# f103.net
KiCad netlist of a schematic drawn in Altium Designer
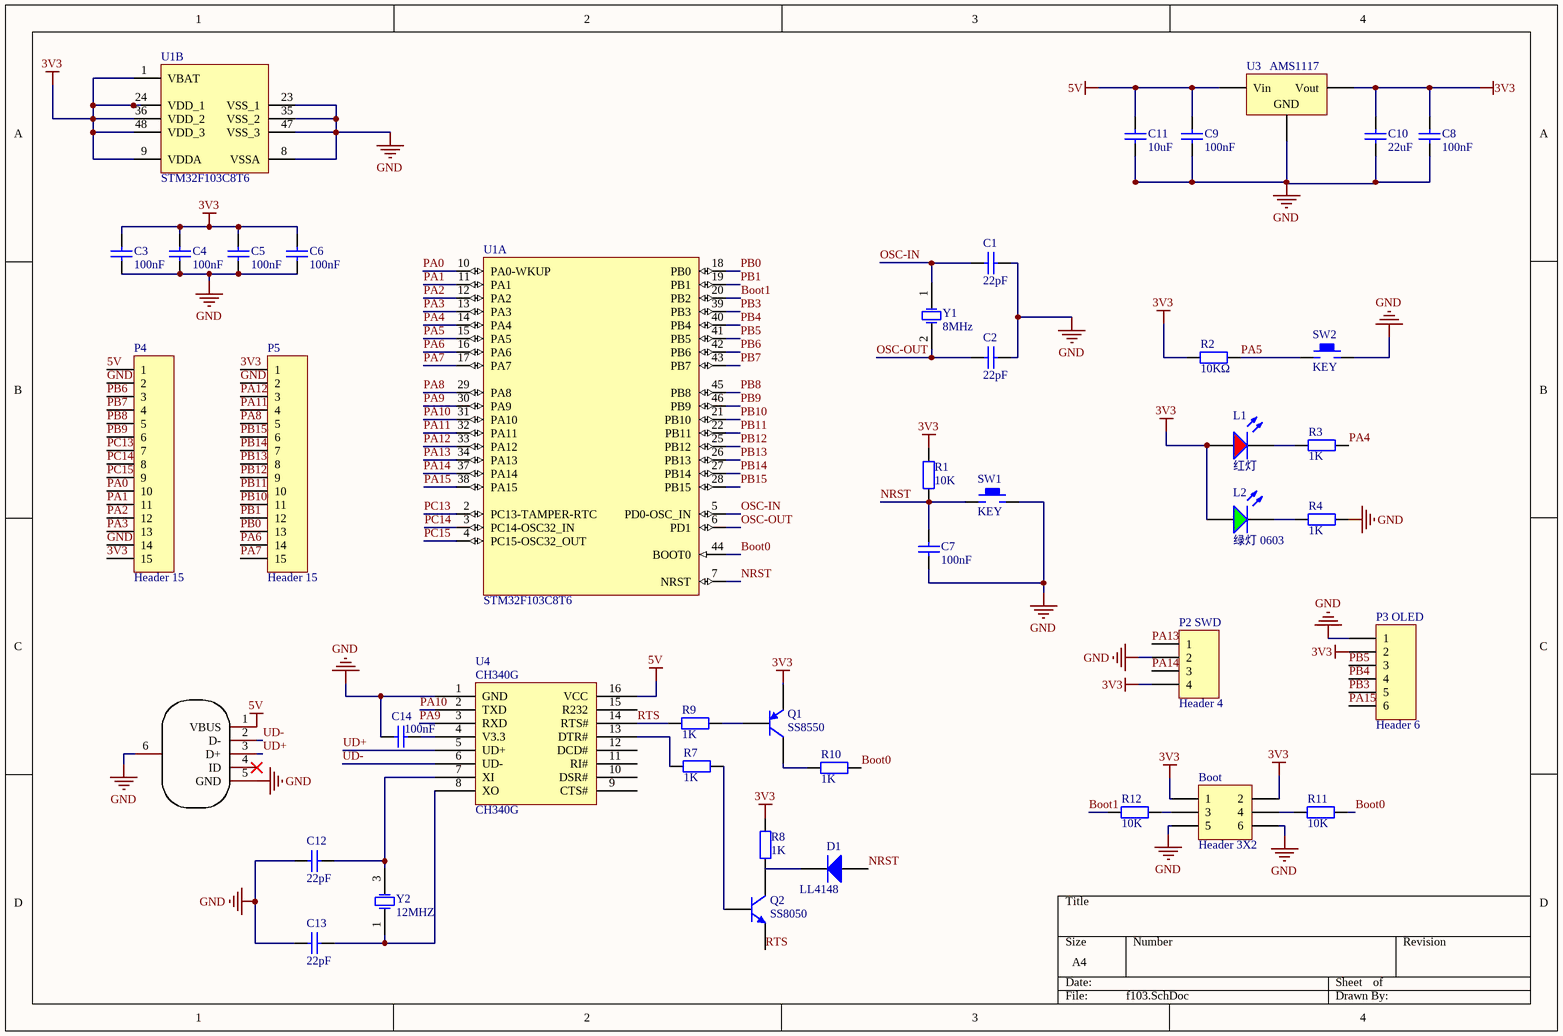
[diagram p0: f103.SchDoc]

(export (version "E")
  (design (tool "Eeschema 10.0.6"))
  (components
    (comp (ref "Boot")
      (value "Header 3X2")
      (footprint "HDR2X3")
      (description "Header, 3-Pin, Dual row")
      (fields (field (name "PUBLISHER") "Altium Limited"))
      (libsource (lib "Miscellaneous Connectors") (part "Header 3X2"))
    )
    (comp (ref "C1")
      (value "22pF")
      (footprint "0603_C")
      (description "贴片电容")
      (libsource (lib "Miscellaneous Devices LC") (part "0603 22pF (220) 5% 50V"))
    )
    (comp (ref "C2")
      (value "22pF")
      (footprint "0603_C")
      (description "贴片电容")
      (libsource (lib "Miscellaneous Devices LC") (part "0603 22pF (220) 5% 50V"))
    )
    (comp (ref "C3")
      (value "100nF")
      (footprint "0603_C")
      (description "贴片电容")
      (libsource (lib "Miscellaneous Devices LC") (part "0603 100nF (104) 10% 50V"))
    )
    (comp (ref "C4")
      (value "100nF")
      (footprint "0603_C")
      (description "贴片电容")
      (libsource (lib "Miscellaneous Devices LC") (part "0603 100nF (104) 10% 50V"))
    )
    (comp (ref "C5")
      (value "100nF")
      (footprint "0603_C")
      (description "贴片电容")
      (libsource (lib "Miscellaneous Devices LC") (part "0603 100nF (104) 10% 50V"))
    )
    (comp (ref "C6")
      (value "100nF")
      (footprint "0603_C")
      (description "贴片电容")
      (libsource (lib "Miscellaneous Devices LC") (part "0603 100nF (104) 10% 50V"))
    )
    (comp (ref "C7")
      (value "100nF")
      (footprint "0603_C")
      (description "贴片电容")
      (libsource (lib "Miscellaneous Devices LC") (part "0603 100nF (104) 10% 50V"))
    )
    (comp (ref "C8")
      (value "100nF")
      (footprint "0603_C")
      (description "贴片电容")
      (libsource (lib "Miscellaneous Devices LC") (part "0603 100nF (104) 10% 50V"))
    )
    (comp (ref "C9")
      (value "100nF")
      (footprint "0603_C")
      (description "贴片电容")
      (libsource (lib "Miscellaneous Devices LC") (part "0603 100nF (104) 10% 50V"))
    )
    (comp (ref "C10")
      (value "22uF")
      (footprint "0603_C")
      (description "贴片电容")
      (libsource (lib "Miscellaneous Devices LC") (part "0603 22uF (226) 20% 6.3V"))
    )
    (comp (ref "C11")
      (value "10uF")
      (footprint "0603_C")
      (description "贴片电容")
      (libsource (lib "Miscellaneous Devices LC") (part "0603 10uF (106) 10% 10V"))
    )
    (comp (ref "C12")
      (value "22pF")
      (footprint "0603_C")
      (description "贴片电容")
      (libsource (lib "Miscellaneous Devices LC") (part "0603 22pF (220) 5% 50V"))
    )
    (comp (ref "C13")
      (value "22pF")
      (footprint "0603_C")
      (description "贴片电容")
      (libsource (lib "Miscellaneous Devices LC") (part "0603 22pF (220) 5% 50V"))
    )
    (comp (ref "C14")
      (value "100nF")
      (footprint "0603_C")
      (description "贴片电容")
      (libsource (lib "Miscellaneous Devices LC") (part "0603 100nF (104) 10% 50V"))
    )
    (comp (ref "D1")
      (value "LL4148")
      (footprint "LL-34")
      (description "开关二极管")
      (libsource (lib "Miscellaneous Devices LC") (part "LL-34 LL4148 LL-34 1206"))
    )
    (comp (ref "L1")
      (value "红灯")
      (footprint "0603_LED_S1")
      (description "发光二极管")
      (libsource (lib "Miscellaneous Devices LC") (part "0603 红灯"))
    )
    (comp (ref "L2")
      (value "绿灯 0603")
      (footprint "0603_LED_S1")
      (description "发光二极管")
      (libsource (lib "Miscellaneous Devices LC") (part "0603 绿灯"))
    )
    (comp (ref "P2 SWD")
      (value "Header 4")
      (footprint "HDR1X4")
      (description "Header, 4-Pin")
      (fields (field (name "PUBLISHER") "Altium Limited"))
      (libsource (lib "Miscellaneous Connectors") (part "Header 4"))
    )
    (comp (ref "P3 OLED")
      (value "Header 6")
      (footprint "HDR1X6")
      (description "Header, 6-Pin")
      (fields (field (name "PUBLISHER") "Altium Limited"))
      (libsource (lib "Miscellaneous Connectors") (part "Header 6"))
    )
    (comp (ref "P4")
      (value "Header 15")
      (footprint "HDR1X15")
      (description "Header, 15-Pin")
      (fields (field (name "PUBLISHER") "Altium Limited"))
      (libsource (lib "Miscellaneous Connectors") (part "Header 15"))
    )
    (comp (ref "P5")
      (value "Header 15")
      (footprint "HDR1X15")
      (description "Header, 15-Pin")
      (fields (field (name "PUBLISHER") "Altium Limited"))
      (libsource (lib "Miscellaneous Connectors") (part "Header 15"))
    )
    (comp (ref "Q1")
      (value "SS8550")
      (footprint "SOT-23(SOT-23-3)")
      (description "三极管")
      (libsource (lib "Miscellaneous Devices LC") (part "SOT-23 SS8550 Y2"))
    )
    (comp (ref "Q2")
      (value "SS8050")
      (footprint "SOT-23(SOT-23-3)")
      (description "三极管")
      (libsource (lib "Miscellaneous Devices LC") (part "SOT-23 SS8050 Y1"))
    )
    (comp (ref "R1")
      (value "10K")
      (footprint "0603_R")
      (description "贴片电阻")
      (libsource (lib "Miscellaneous Devices LC") (part "0603 10KΩ (1002) 1%"))
    )
    (comp (ref "R2")
      (value "10KΩ")
      (footprint "0603_R")
      (description "贴片电阻")
      (libsource (lib "") (part "0603 10KΩ (1002) 1%_1"))
    )
    (comp (ref "R3")
      (value "1K")
      (footprint "0603_R")
      (description "贴片电阻")
      (libsource (lib "Miscellaneous Devices LC") (part "0603 1KΩ (1001) 1%"))
    )
    (comp (ref "R4")
      (value "1K")
      (footprint "0603_R")
      (description "贴片电阻")
      (libsource (lib "Miscellaneous Devices LC") (part "0603 1KΩ (1001) 1%"))
    )
    (comp (ref "R7")
      (value "1K")
      (footprint "0603_R")
      (description "贴片电阻")
      (libsource (lib "Miscellaneous Devices LC") (part "0603 1KΩ (1001) 1%"))
    )
    (comp (ref "R8")
      (value "1K")
      (footprint "0603_R")
      (description "贴片电阻")
      (libsource (lib "") (part "0603 1KΩ (1001) 1%_1"))
    )
    (comp (ref "R9")
      (value "1K")
      (footprint "0603_R")
      (description "贴片电阻")
      (libsource (lib "Miscellaneous Devices LC") (part "0603 1KΩ (1001) 1%"))
    )
    (comp (ref "R10")
      (value "1K")
      (footprint "0603_R")
      (description "贴片电阻")
      (libsource (lib "Miscellaneous Devices LC") (part "0603 1KΩ (1001) 1%"))
    )
    (comp (ref "R11")
      (value "10K")
      (footprint "0603_R")
      (description "贴片电阻")
      (libsource (lib "") (part "0603 10KΩ (1002) 1%_1"))
    )
    (comp (ref "R12")
      (value "10K")
      (footprint "0603_R")
      (description "贴片电阻")
      (libsource (lib "") (part "0603 10KΩ (1002) 1%_1"))
    )
    (comp (ref "SW1") (value "KEY") (footprint "KEY_M") (libsource (lib "MiniFly ") (part "KEY")))
    (comp (ref "SW2") (value "KEY") (footprint "KEY_M") (libsource (lib "MiniFly ") (part "KEY")))
    (comp (ref "U1")
      (value "STM32F103C8T6")
      (footprint "LQFP-48_7x7x05P")
      (description "ARM")
      (libsource (lib "Miscellaneous Devices LC") (part "STM32F103C8T6"))
    )
    (comp (ref "U3")
      (value "AMS1117")
      (footprint "SOT-223")
      (description "低压差线性稳压(LDO)")
      (libsource (lib "Miscellaneous Devices LC") (part "SOT-223 AMS1117-3.3"))
    )
    (comp (ref "U4")
      (value "CH340G")
      (footprint "SOIC-16_150mil")
      (description "USB")
      (libsource (lib "Miscellaneous Devices LC") (part "CH340G_[C14267]"))
    )
    (comp (ref "USB")
      (value "U254-051T-4BH23-S2S")
      (footprint "MICRO-USB-SMD_U254-051T-4BH23-S2S")
      (fields (field (name "MANUFACTURER") "XKB Connectivity(中国星坤)"))
      (libsource (lib "embedi") (part "U254-051T-4BH23-S2S"))
    )
    (comp (ref "Y1")
      (value "8MHz")
      (footprint "SMD-5032_2P")
      (description "贴片晶振")
      (libsource (lib "Miscellaneous Devices LC") (part "SMD-5032_2P 8MHz 20ppm 20pF"))
    )
    (comp (ref "Y2")
      (value "12MHZ")
      (footprint "SMD-3225_4P")
      (description "贴片晶振")
      (libsource (lib "Miscellaneous Devices LC") (part "SMD-3225_4P  12MHZ 20PF 10PPM"))
    )
  )
  (nets
    (net (code "2") (name "/Boot0") (class "Default")
      (node (ref "R10") (pin "2") (pinfunction "2_2") (pintype "passive"))
      (node (ref "R11") (pin "2") (pinfunction "2_2") (pintype "passive"))
      (node (ref "U1") (pin "44") (pinfunction "BOOT0_44") (pintype "input"))
    )
    (net (code "3") (name "/Boot1") (class "Default")
      (node (ref "R12") (pin "1") (pinfunction "1_1") (pintype "passive"))
      (node (ref "U1") (pin "20") (pinfunction "PB2_20") (pintype "bidirectional"))
    )
    (net (code "4") (name "/NRST") (class "Default")
      (node (ref "C7") (pin "2") (pinfunction "2_2") (pintype "passive"))
      (node (ref "D1") (pin "1") (pinfunction "A_1") (pintype "passive"))
      (node (ref "R1") (pin "1") (pinfunction "1_1") (pintype "passive"))
      (node (ref "SW1") (pin "1") (pinfunction "1_1") (pintype "passive"))
      (node (ref "U1") (pin "7") (pinfunction "NRST_7") (pintype "bidirectional"))
    )
    (net (code "5") (name "/OSC-IN") (class "Default")
      (node (ref "C1") (pin "2") (pinfunction "2_2") (pintype "passive"))
      (node (ref "U1") (pin "5") (pinfunction "PD0-OSC_IN_5") (pintype "bidirectional"))
      (node (ref "Y1") (pin "1") (pinfunction "OSC1_1") (pintype "passive"))
    )
    (net (code "6") (name "/OSC-OUT") (class "Default")
      (node (ref "C2") (pin "2") (pinfunction "2_2") (pintype "passive"))
      (node (ref "U1") (pin "6") (pinfunction "PD1_6") (pintype "bidirectional"))
      (node (ref "Y1") (pin "2") (pinfunction "OSC2_2") (pintype "passive"))
    )
    (net (code "7") (name "/PA0") (class "Default")
      (node (ref "P4") (pin "10") (pinfunction "10_10") (pintype "passive"))
      (node (ref "U1") (pin "10") (pinfunction "PA0-WKUP_10") (pintype "bidirectional"))
    )
    (net (code "8") (name "/PA1") (class "Default")
      (node (ref "P4") (pin "11") (pinfunction "11_11") (pintype "passive"))
      (node (ref "U1") (pin "11") (pinfunction "PA1_11") (pintype "bidirectional"))
    )
    (net (code "9") (name "/PA2") (class "Default")
      (node (ref "P4") (pin "12") (pinfunction "12_12") (pintype "passive"))
      (node (ref "U1") (pin "12") (pinfunction "PA2_12") (pintype "bidirectional"))
    )
    (net (code "10") (name "/PA3") (class "Default")
      (node (ref "P4") (pin "13") (pinfunction "13_13") (pintype "passive"))
      (node (ref "U1") (pin "13") (pinfunction "PA3_13") (pintype "bidirectional"))
    )
    (net (code "11") (name "/PA4") (class "Default")
      (node (ref "R3") (pin "2") (pinfunction "2_2") (pintype "passive"))
      (node (ref "U1") (pin "14") (pinfunction "PA4_14") (pintype "bidirectional"))
    )
    (net (code "12") (name "/PA5") (class "Default")
      (node (ref "R2") (pin "2") (pinfunction "2_2") (pintype "passive"))
      (node (ref "SW2") (pin "1") (pinfunction "1_1") (pintype "passive"))
      (node (ref "U1") (pin "15") (pinfunction "PA5_15") (pintype "bidirectional"))
    )
    (net (code "13") (name "/PA6") (class "Default")
      (node (ref "P5") (pin "14") (pinfunction "14_14") (pintype "passive"))
      (node (ref "U1") (pin "16") (pinfunction "PA6_16") (pintype "bidirectional"))
    )
    (net (code "14") (name "/PA7") (class "Default")
      (node (ref "P5") (pin "15") (pinfunction "15_15") (pintype "passive"))
      (node (ref "U1") (pin "17") (pinfunction "PA7_17") (pintype "bidirectional"))
    )
    (net (code "15") (name "/PA8") (class "Default")
      (node (ref "P5") (pin "5") (pinfunction "5_5") (pintype "passive"))
      (node (ref "U1") (pin "29") (pinfunction "PA8_29") (pintype "bidirectional"))
    )
    (net (code "16") (name "/PA9") (class "Default")
      (node (ref "U1") (pin "30") (pinfunction "PA9_30") (pintype "bidirectional"))
      (node (ref "U4") (pin "3") (pinfunction "RXD_3") (pintype "passive"))
    )
    (net (code "17") (name "/PA10") (class "Default")
      (node (ref "U1") (pin "31") (pinfunction "PA10_31") (pintype "bidirectional"))
      (node (ref "U4") (pin "2") (pinfunction "TXD_2") (pintype "passive"))
    )
    (net (code "18") (name "/PA11") (class "Default")
      (node (ref "P5") (pin "4") (pinfunction "4_4") (pintype "passive"))
      (node (ref "U1") (pin "32") (pinfunction "PA11_32") (pintype "bidirectional"))
    )
    (net (code "19") (name "/PA12") (class "Default")
      (node (ref "P5") (pin "3") (pinfunction "3_3") (pintype "passive"))
      (node (ref "U1") (pin "33") (pinfunction "PA12_33") (pintype "bidirectional"))
    )
    (net (code "20") (name "/PA13") (class "Default")
      (node (ref "P2 SWD") (pin "1") (pinfunction "1_1") (pintype "passive"))
      (node (ref "U1") (pin "34") (pinfunction "PA13_34") (pintype "bidirectional"))
    )
    (net (code "21") (name "/PA14") (class "Default")
      (node (ref "P2 SWD") (pin "3") (pinfunction "3_3") (pintype "passive"))
      (node (ref "U1") (pin "37") (pinfunction "PA14_37") (pintype "bidirectional"))
    )
    (net (code "22") (name "/PA15") (class "Default")
      (node (ref "P3 OLED") (pin "6") (pinfunction "6_6") (pintype "passive"))
      (node (ref "U1") (pin "38") (pinfunction "PA15_38") (pintype "bidirectional"))
    )
    (net (code "23") (name "/PB0") (class "Default")
      (node (ref "P5") (pin "13") (pinfunction "13_13") (pintype "passive"))
      (node (ref "U1") (pin "18") (pinfunction "PB0_18") (pintype "bidirectional"))
    )
    (net (code "24") (name "/PB1") (class "Default")
      (node (ref "P5") (pin "12") (pinfunction "12_12") (pintype "passive"))
      (node (ref "U1") (pin "19") (pinfunction "PB1_19") (pintype "bidirectional"))
    )
    (net (code "25") (name "/PB3") (class "Default")
      (node (ref "P3 OLED") (pin "5") (pinfunction "5_5") (pintype "passive"))
      (node (ref "U1") (pin "39") (pinfunction "PB3_39") (pintype "bidirectional"))
    )
    (net (code "26") (name "/PB4") (class "Default")
      (node (ref "P3 OLED") (pin "4") (pinfunction "4_4") (pintype "passive"))
      (node (ref "U1") (pin "40") (pinfunction "PB4_40") (pintype "bidirectional"))
    )
    (net (code "27") (name "/PB5") (class "Default")
      (node (ref "P3 OLED") (pin "3") (pinfunction "3_3") (pintype "passive"))
      (node (ref "U1") (pin "41") (pinfunction "PB5_41") (pintype "bidirectional"))
    )
    (net (code "28") (name "/PB6") (class "Default")
      (node (ref "P4") (pin "3") (pinfunction "3_3") (pintype "passive"))
      (node (ref "U1") (pin "42") (pinfunction "PB6_42") (pintype "bidirectional"))
    )
    (net (code "29") (name "/PB7") (class "Default")
      (node (ref "P4") (pin "4") (pinfunction "4_4") (pintype "passive"))
      (node (ref "U1") (pin "43") (pinfunction "PB7_43") (pintype "bidirectional"))
    )
    (net (code "30") (name "/PB8") (class "Default")
      (node (ref "P4") (pin "5") (pinfunction "5_5") (pintype "passive"))
      (node (ref "U1") (pin "45") (pinfunction "PB8_45") (pintype "bidirectional"))
    )
    (net (code "31") (name "/PB9") (class "Default")
      (node (ref "P4") (pin "6") (pinfunction "6_6") (pintype "passive"))
      (node (ref "U1") (pin "46") (pinfunction "PB9_46") (pintype "bidirectional"))
    )
    (net (code "32") (name "/PB10") (class "Default")
      (node (ref "P5") (pin "11") (pinfunction "11_11") (pintype "passive"))
      (node (ref "U1") (pin "21") (pinfunction "PB10_21") (pintype "bidirectional"))
    )
    (net (code "33") (name "/PB11") (class "Default")
      (node (ref "P5") (pin "10") (pinfunction "10_10") (pintype "passive"))
      (node (ref "U1") (pin "22") (pinfunction "PB11_22") (pintype "bidirectional"))
    )
    (net (code "34") (name "/PB12") (class "Default")
      (node (ref "P5") (pin "9") (pinfunction "9_9") (pintype "passive"))
      (node (ref "U1") (pin "25") (pinfunction "PB12_25") (pintype "bidirectional"))
    )
    (net (code "35") (name "/PB13") (class "Default")
      (node (ref "P5") (pin "8") (pinfunction "8_8") (pintype "passive"))
      (node (ref "U1") (pin "26") (pinfunction "PB13_26") (pintype "bidirectional"))
    )
    (net (code "36") (name "/PB14") (class "Default")
      (node (ref "P5") (pin "7") (pinfunction "7_7") (pintype "passive"))
      (node (ref "U1") (pin "27") (pinfunction "PB14_27") (pintype "bidirectional"))
    )
    (net (code "37") (name "/PB15") (class "Default")
      (node (ref "P5") (pin "6") (pinfunction "6_6") (pintype "passive"))
      (node (ref "U1") (pin "28") (pinfunction "PB15_28") (pintype "bidirectional"))
    )
    (net (code "38") (name "/PC13") (class "Default")
      (node (ref "P4") (pin "7") (pinfunction "7_7") (pintype "passive"))
      (node (ref "U1") (pin "2") (pinfunction "PC13-TAMPER-RTC_2") (pintype "bidirectional"))
    )
    (net (code "39") (name "/PC14") (class "Default")
      (node (ref "P4") (pin "8") (pinfunction "8_8") (pintype "passive"))
      (node (ref "U1") (pin "3") (pinfunction "PC14-OSC32_IN_3") (pintype "bidirectional"))
    )
    (net (code "40") (name "/PC15") (class "Default")
      (node (ref "P4") (pin "9") (pinfunction "9_9") (pintype "passive"))
      (node (ref "U1") (pin "4") (pinfunction "PC15-OSC32_OUT_4") (pintype "bidirectional"))
    )
    (net (code "41") (name "/RTS") (class "Default")
      (node (ref "Q2") (pin "2") (pinfunction "E_2") (pintype "passive"))
      (node (ref "R9") (pin "1") (pinfunction "1_1") (pintype "passive"))
      (node (ref "U4") (pin "14") (pinfunction "RTS#_14") (pintype "passive"))
    )
    (net (code "42") (name "/UD+") (class "Default")
      (node (ref "U4") (pin "5") (pinfunction "UD+_5") (pintype "passive"))
      (node (ref "USB") (pin "3") (pinfunction "D+_3") (pintype "passive"))
    )
    (net (code "43") (name "/UD-") (class "Default")
      (node (ref "U4") (pin "6") (pinfunction "UD-_6") (pintype "passive"))
      (node (ref "USB") (pin "2") (pinfunction "D-_2") (pintype "passive"))
    )
    (net (code "44") (name "3V3") (class "Default")
      (node (ref "Boot") (pin "1") (pinfunction "1_1") (pintype "passive"))
      (node (ref "Boot") (pin "2") (pinfunction "2_2") (pintype "passive"))
      (node (ref "C10") (pin "1") (pinfunction "1_1") (pintype "passive"))
      (node (ref "C3") (pin "2") (pinfunction "2_2") (pintype "passive"))
      (node (ref "C4") (pin "2") (pinfunction "2_2") (pintype "passive"))
      (node (ref "C5") (pin "2") (pinfunction "2_2") (pintype "passive"))
      (node (ref "C6") (pin "2") (pinfunction "2_2") (pintype "passive"))
      (node (ref "C8") (pin "2") (pinfunction "2_2") (pintype "passive"))
      (node (ref "L1") (pin "A") (pinfunction "A_A") (pintype "passive"))
      (node (ref "L2") (pin "A") (pinfunction "A_A") (pintype "passive"))
      (node (ref "P2 SWD") (pin "4") (pinfunction "4_4") (pintype "passive"))
      (node (ref "P3 OLED") (pin "2") (pinfunction "2_2") (pintype "passive"))
      (node (ref "P4") (pin "15") (pinfunction "15_15") (pintype "passive"))
      (node (ref "P5") (pin "1") (pinfunction "1_1") (pintype "passive"))
      (node (ref "Q1") (pin "2") (pinfunction "E_2") (pintype "passive"))
      (node (ref "R1") (pin "2") (pinfunction "2_2") (pintype "passive"))
      (node (ref "R2") (pin "1") (pinfunction "1_1") (pintype "passive"))
      (node (ref "R8") (pin "2") (pinfunction "2_2") (pintype "passive"))
      (node (ref "U1") (pin "1") (pinfunction "VBAT_1") (pintype "power_in"))
      (node (ref "U1") (pin "24") (pinfunction "VDD_1_24") (pintype "power_in"))
      (node (ref "U1") (pin "36") (pinfunction "VDD_2_36") (pintype "power_in"))
      (node (ref "U1") (pin "48") (pinfunction "VDD_3_48") (pintype "power_in"))
      (node (ref "U1") (pin "9") (pinfunction "VDDA_9") (pintype "power_in"))
      (node (ref "U3") (pin "2") (pinfunction "Vout_2") (pintype "passive"))
    )
    (net (code "45") (name "5V") (class "Default")
      (node (ref "C11") (pin "1") (pinfunction "1_1") (pintype "passive"))
      (node (ref "C9") (pin "2") (pinfunction "2_2") (pintype "passive"))
      (node (ref "P4") (pin "1") (pinfunction "1_1") (pintype "passive"))
      (node (ref "U3") (pin "3") (pinfunction "Vin_3") (pintype "passive"))
      (node (ref "U4") (pin "16") (pinfunction "VCC_16") (pintype "passive"))
      (node (ref "USB") (pin "1") (pinfunction "VBUS_1") (pintype "passive"))
    )
    (net (code "46") (name "GND") (class "Default")
      (node (ref "Boot") (pin "5") (pinfunction "5_5") (pintype "passive"))
      (node (ref "Boot") (pin "6") (pinfunction "6_6") (pintype "passive"))
      (node (ref "C1") (pin "1") (pinfunction "1_1") (pintype "passive"))
      (node (ref "C10") (pin "2") (pinfunction "2_2") (pintype "passive"))
      (node (ref "C11") (pin "2") (pinfunction "2_2") (pintype "passive"))
      (node (ref "C12") (pin "1") (pinfunction "1_1") (pintype "passive"))
      (node (ref "C13") (pin "1") (pinfunction "1_1") (pintype "passive"))
      (node (ref "C14") (pin "1") (pinfunction "1_1") (pintype "passive"))
      (node (ref "C2") (pin "1") (pinfunction "1_1") (pintype "passive"))
      (node (ref "C3") (pin "1") (pinfunction "1_1") (pintype "passive"))
      (node (ref "C4") (pin "1") (pinfunction "1_1") (pintype "passive"))
      (node (ref "C5") (pin "1") (pinfunction "1_1") (pintype "passive"))
      (node (ref "C6") (pin "1") (pinfunction "1_1") (pintype "passive"))
      (node (ref "C7") (pin "1") (pinfunction "1_1") (pintype "passive"))
      (node (ref "C8") (pin "1") (pinfunction "1_1") (pintype "passive"))
      (node (ref "C9") (pin "1") (pinfunction "1_1") (pintype "passive"))
      (node (ref "P2 SWD") (pin "2") (pinfunction "2_2") (pintype "passive"))
      (node (ref "P3 OLED") (pin "1") (pinfunction "1_1") (pintype "passive"))
      (node (ref "P4") (pin "14") (pinfunction "14_14") (pintype "passive"))
      (node (ref "P4") (pin "2") (pinfunction "2_2") (pintype "passive"))
      (node (ref "P5") (pin "2") (pinfunction "2_2") (pintype "passive"))
      (node (ref "R4") (pin "2") (pinfunction "2_2") (pintype "passive"))
      (node (ref "SW1") (pin "2") (pinfunction "2_2") (pintype "passive"))
      (node (ref "SW2") (pin "2") (pinfunction "2_2") (pintype "passive"))
      (node (ref "U1") (pin "23") (pinfunction "VSS_1_23") (pintype "power_in"))
      (node (ref "U1") (pin "35") (pinfunction "VSS_2_35") (pintype "power_in"))
      (node (ref "U1") (pin "47") (pinfunction "VSS_3_47") (pintype "power_in"))
      (node (ref "U1") (pin "8") (pinfunction "VSSA_8") (pintype "power_in"))
      (node (ref "U3") (pin "1") (pinfunction "GND_1") (pintype "passive"))
      (node (ref "U4") (pin "1") (pinfunction "GND_1") (pintype "passive"))
      (node (ref "USB") (pin "5") (pinfunction "GND_5") (pintype "passive"))
      (node (ref "USB") (pin "6") (pinfunction "EH_6") (pintype "passive"))
    )
    (net (code "47") (name "Net-(Boot-Pad3)") (class "Default")
      (node (ref "Boot") (pin "3") (pinfunction "3_3") (pintype "passive"))
      (node (ref "R12") (pin "2") (pinfunction "2_2") (pintype "passive"))
    )
    (net (code "48") (name "Net-(Boot-Pad4)") (class "Default")
      (node (ref "Boot") (pin "4") (pinfunction "4_4") (pintype "passive"))
      (node (ref "R11") (pin "1") (pinfunction "1_1") (pintype "passive"))
    )
    (net (code "49") (name "Net-(D1-K)") (class "Default")
      (node (ref "D1") (pin "2") (pinfunction "K_2") (pintype "passive"))
      (node (ref "Q2") (pin "3") (pinfunction "C_3") (pintype "passive"))
    )
    (net (code "50") (name "Net-(L1-PadK)") (class "Default")
      (node (ref "L1") (pin "K") (pinfunction "K_K") (pintype "passive"))
      (node (ref "R3") (pin "1") (pinfunction "1_1") (pintype "passive"))
    )
    (net (code "51") (name "Net-(L2-PadK)") (class "Default")
      (node (ref "L2") (pin "K") (pinfunction "K_K") (pintype "passive"))
      (node (ref "R4") (pin "1") (pinfunction "1_1") (pintype "passive"))
    )
    (net (code "52") (name "Net-(Q1-B)") (class "Default")
      (node (ref "Q1") (pin "1") (pinfunction "B_1") (pintype "passive"))
      (node (ref "R9") (pin "2") (pinfunction "2_2") (pintype "passive"))
    )
    (net (code "53") (name "Net-(Q1-C)") (class "Default")
      (node (ref "Q1") (pin "3") (pinfunction "C_3") (pintype "passive"))
      (node (ref "R10") (pin "1") (pinfunction "1_1") (pintype "passive"))
    )
    (net (code "54") (name "Net-(Q2-B)") (class "Default")
      (node (ref "Q2") (pin "1") (pinfunction "B_1") (pintype "passive"))
      (node (ref "R7") (pin "2") (pinfunction "2_2") (pintype "passive"))
    )
    (net (code "55") (name "Net-(U4-DTR#)") (class "Default")
      (node (ref "R7") (pin "1") (pinfunction "1_1") (pintype "passive"))
      (node (ref "U4") (pin "13") (pinfunction "DTR#_13") (pintype "passive"))
    )
    (net (code "56") (name "Net-(U4-V3.3)") (class "Default")
      (node (ref "C14") (pin "2") (pinfunction "2_2") (pintype "passive"))
      (node (ref "U4") (pin "4") (pinfunction "V3.3_4") (pintype "passive"))
    )
    (net (code "57") (name "Net-(U4-XI)") (class "Default")
      (node (ref "C12") (pin "2") (pinfunction "2_2") (pintype "passive"))
      (node (ref "U4") (pin "7") (pinfunction "XI_7") (pintype "passive"))
      (node (ref "Y2") (pin "3") (pinfunction "OSC2_3") (pintype "passive"))
    )
    (net (code "58") (name "Net-(U4-XO)") (class "Default")
      (node (ref "C13") (pin "2") (pinfunction "2_2") (pintype "passive"))
      (node (ref "U4") (pin "8") (pinfunction "XO_8") (pintype "passive"))
      (node (ref "Y2") (pin "1") (pinfunction "OSC1_1") (pintype "passive"))
    )
    (net (code "59") (name "unconnected-(R8-Pad1)") (class "Default")
      (node (ref "R8") (pin "1") (pinfunction "1_1") (pintype "passive"))
    )
    (net (code "60") (name "unconnected-(U4-CTS#-Pad9)") (class "Default")
      (node (ref "U4") (pin "9") (pinfunction "CTS#_9") (pintype "passive"))
    )
    (net (code "61") (name "unconnected-(U4-DCD#-Pad12)") (class "Default")
      (node (ref "U4") (pin "12") (pinfunction "DCD#_12") (pintype "passive"))
    )
    (net (code "62") (name "unconnected-(U4-DSR#-Pad10)") (class "Default")
      (node (ref "U4") (pin "10") (pinfunction "DSR#_10") (pintype "passive"))
    )
    (net (code "63") (name "unconnected-(U4-R232-Pad15)") (class "Default")
      (node (ref "U4") (pin "15") (pinfunction "R232_15") (pintype "passive"))
    )
    (net (code "64") (name "unconnected-(U4-RI#-Pad11)") (class "Default")
      (node (ref "U4") (pin "11") (pinfunction "RI#_11") (pintype "passive"))
    )
    (net (code "65") (name "unconnected-(USB-ID-Pad4)") (class "Default")
      (node (ref "USB") (pin "4") (pinfunction "ID_4") (pintype "passive+no_connect"))
    )
  )
)
